# Supplies.net
KiCad netlist of a schematic drawn in Altium Designer
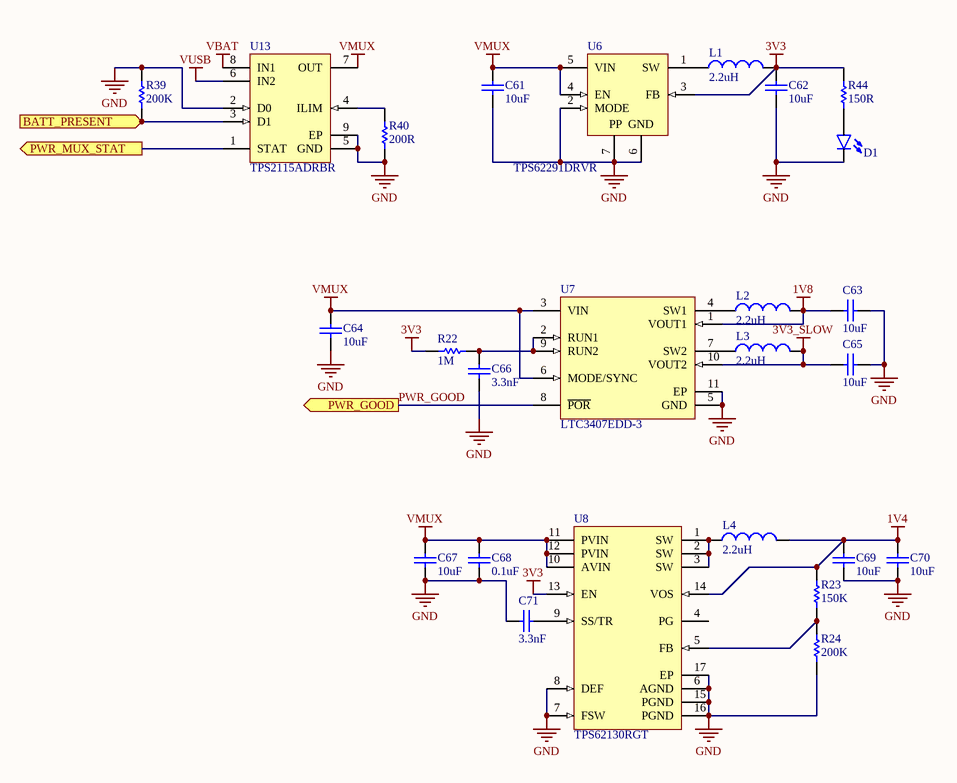
[diagram p0: Supplies.SchDoc]

(export (version "E")
  (design (tool "Eeschema 10.0.6"))
  (components
    (comp (ref "C61")
      (value "10uF")
      (footprint "C0402[1005X55]")
      (description "10uF 6.3V 20% 0402 (1005 Metric)")
      (fields (field (name "TOLERANCE") "20%") (field (name "PARTNUMBER") "GRM155R60J106ME44D"))
      (libsource (lib "Capacitors") (part "CAP_10uF_6.3V_0402_20%"))
    )
    (comp (ref "C62")
      (value "10uF")
      (footprint "C0402[1005X55]")
      (description "10uF 6.3V 20% 0402 (1005 Metric)")
      (fields (field (name "TOLERANCE") "20%") (field (name "PARTNUMBER") "GRM155R60J106ME44D"))
      (libsource (lib "Capacitors") (part "CAP_10uF_6.3V_0402_20%"))
    )
    (comp (ref "C63")
      (value "10uF")
      (footprint "C0402[1005X55]")
      (description "10uF 6.3V 20% 0402 (1005 Metric)")
      (fields (field (name "PARTNUMBER") "GRM155R60J106ME44D") (field (name "MANUFACTURER") "Murata"))
      (libsource (lib "Capacitors") (part "CAP_10uF_6.3V_0402_20%"))
    )
    (comp (ref "C64")
      (value "10uF")
      (footprint "C0402[1005X55]")
      (description "10uF 6.3V 20% 0402 (1005 Metric)")
      (fields (field (name "PARTNUMBER") "GRM155R60J106ME44D") (field (name "MANUFACTURER") "Murata"))
      (libsource (lib "Capacitors") (part "CAP_10uF_6.3V_0402_20%"))
    )
    (comp (ref "C65")
      (value "10uF")
      (footprint "C0402[1005X55]")
      (description "10uF 6.3V 20% 0402 (1005 Metric)")
      (fields (field (name "PARTNUMBER") "GRM155R60J106ME44D") (field (name "MANUFACTURER") "Murata"))
      (libsource (lib "Capacitors") (part "CAP_10uF_6.3V_0402_20%"))
    )
    (comp (ref "C66")
      (value "3.3nF")
      (footprint "C0402[1005X55]")
      (description "3.3nF 50V 10% 0402 (1005 Metric)")
      (fields (field (name "PARTNUMBER") "GRM155R71H332KA01D") (field (name "MANUFACTURER") "Murata"))
      (libsource (lib "Capacitors") (part "CAP_3.3nF_50V_0402_10%"))
    )
    (comp (ref "C67")
      (value "10uF")
      (footprint "C0402[1005X55]")
      (description "10uF 6.3V 20% 0402 (1005 Metric)")
      (fields (field (name "PARTNUMBER") "GRM155R60J106ME44D") (field (name "MANUFACTURER") "Murata"))
      (libsource (lib "Capacitors") (part "CAP_10uF_6.3V_0402_20%"))
    )
    (comp (ref "C68")
      (value "0.1uF")
      (footprint "C0402[1005X55]")
      (description "0.1uF 6.3V 10% 0402 (1005 Metric)")
      (fields (field (name "PARTNUMBER") "GRM155R70J104KA01D") (field (name "MANUFACTURER") "Murata"))
      (libsource (lib "Capacitors") (part "CAP_0.1uF_6.3V_0402_10%"))
    )
    (comp (ref "C69")
      (value "10uF")
      (footprint "C0402[1005X55]")
      (description "10uF 6.3V 20% 0402 (1005 Metric)")
      (fields (field (name "PARTNUMBER") "GRM155R60J106ME44D") (field (name "MANUFACTURER") "Murata"))
      (libsource (lib "Capacitors") (part "CAP_10uF_6.3V_0402_20%"))
    )
    (comp (ref "C70")
      (value "10uF")
      (footprint "C0402[1005X55]")
      (description "10uF 6.3V 20% 0402 (1005 Metric)")
      (fields (field (name "PARTNUMBER") "GRM155R60J106ME44D") (field (name "MANUFACTURER") "Murata"))
      (libsource (lib "Capacitors") (part "CAP_10uF_6.3V_0402_20%"))
    )
    (comp (ref "C71")
      (value "3.3nF")
      (footprint "C0402[1005X55]")
      (description "3.3nF 50V 10% 0402 (1005 Metric)")
      (fields (field (name "PARTNUMBER") "GRM155R71H332KA01D") (field (name "MANUFACTURER") "Murata"))
      (libsource (lib "Capacitors") (part "CAP_3.3nF_50V_0402_10%"))
    )
    (comp (ref "D1")
      (value "LED_0603_BLUE_5mA")
      (footprint "LED0603")
      (fields (field (name "PARTNUMBER") "LTST-C193TBKT-5A") (field (name "MANUFACTURER") "Lite-On Inc."))
      (libsource (lib "LEDs") (part "LED_0603_BLUE_5mA"))
    )
    (comp (ref "L1")
      (value "2.2uH")
      (footprint "IND0805")
      (description "2.2uH 20% 1.7A 0805")
      (fields (field (name "PARTNUMBER") "LQM21PN2R2MGHL") (field (name "MANUFACTURER") "Murata"))
      (libsource (lib "Inductors") (part "IND_2.2uH_1.7A_0805_20%"))
    )
    (comp (ref "L2")
      (value "2.2uH")
      (footprint "IND0603")
      (description "2.2uH 20% 750mA 0603")
      (fields (field (name "PARTNUMBER") "LQM18PZ2R2MCHD") (field (name "MANUFACTURER") "Murata"))
      (libsource (lib "Inductors") (part "IND_2.2uH_750mA_0603_20%"))
    )
    (comp (ref "L3")
      (value "2.2uH")
      (footprint "IND0603")
      (description "2.2uH 20% 750mA 0603")
      (fields (field (name "PARTNUMBER") "LQM18PZ2R2MCHD") (field (name "MANUFACTURER") "Murata"))
      (libsource (lib "Inductors") (part "IND_2.2uH_750mA_0603_20%"))
    )
    (comp (ref "L4")
      (value "2.2uH")
      (footprint "IND1008")
      (description "2.2uH 20% 3.3A 1008")
      (fields (field (name "PARTNUMBER") "DFE252012F-2R2M=P2") (field (name "MANUFACTURER") "Murata"))
      (libsource (lib "Inductors") (part "IND_2.2uH_3.3A_1008_20%"))
    )
    (comp (ref "R22")
      (value "1M")
      (footprint "R0402[1005]")
      (description "1M 0.063W 1% 0402 (1005 Metric)")
      (fields (field (name "MANUFACTURER") "KOA Speer") (field (name "PARTNUMBER") "RK73H1ETTP1004F"))
      (libsource (lib "Resistors") (part "RES_1M_0402_1%"))
    )
    (comp (ref "R23")
      (value "150K")
      (footprint "R0402[1005]")
      (description "150K 0.063W 1% 0402 (1005 Metric)")
      (fields (field (name "MANUFACTURER") "KOA Speer") (field (name "PARTNUMBER") "RK73H1ETTP1503F"))
      (libsource (lib "Resistors") (part "RES_150K_0402_1%"))
    )
    (comp (ref "R24")
      (value "200K")
      (footprint "R0402[1005]")
      (description "200K 0.063W 1% 0402 (1005 Metric)")
      (fields (field (name "MANUFACTURER") "KOA Speer") (field (name "PARTNUMBER") "RK73H1ETTP2003F"))
      (libsource (lib "Resistors") (part "RES_200K_0402_1%"))
    )
    (comp (ref "R39")
      (value "200K")
      (footprint "R0402[1005]")
      (description "200K 0.063W 1% 0402 (1005 Metric)")
      (fields (field (name "MANUFACTURER") "KOA Speer") (field (name "PARTNUMBER") "RK73H1ETTP2003F"))
      (libsource (lib "Resistors") (part "RES_200K_0402_1%"))
    )
    (comp (ref "R40")
      (value "200R")
      (footprint "R0402[1005]")
      (description "200R 0.063W 1% 0402 (1005 Metric)")
      (fields (field (name "MANUFACTURER") "KOA Speer") (field (name "PARTNUMBER") "RK73H1ETTP2000F"))
      (libsource (lib "Resistors") (part "RES_200R_0402_1%"))
    )
    (comp (ref "R44")
      (value "150R")
      (footprint "R0402[1005]")
      (description "150R 0.063W 1% 0402 (1005 Metric)")
      (fields (field (name "MANUFACTURER") "KOA Speer") (field (name "PARTNUMBER") "RK73H1ETTP1500F"))
      (libsource (lib "Resistors") (part "RES_150R_0402_1%"))
    )
    (comp (ref "U6")
      (value "TPS62291DRVR")
      (footprint "WSON-6")
      (description "Voltage Regulators - Switching Regulators 2.25MHz 1A Step-Down Cnvrtr 3.3V Output")
      (fields (field (name "MANUFACTURER") "Texas Instruments"))
      (libsource (lib "ICs") (part "TPS62291DRVR"))
    )
    (comp (ref "U7")
      (value "LTC3407EDD-3")
      (footprint "VSON-10 (3mmx3mm)")
      (fields (field (name "MANUFACTURER") "Linear Technology"))
      (libsource (lib "ICs") (part "LTC3407EDD-3"))
    )
    (comp (ref "U8")
      (value "TPS62130RGT")
      (footprint "QFN-16")
      (fields (field (name "MANUFACTURER") "Texas Instruments"))
      (libsource (lib "ICs") (part "TPS62130RGT"))
    )
    (comp (ref "U13")
      (value "TPS2115ADRBR")
      (footprint "VSON-8 (3x3MM)")
      (description "Power Switch ICs - Power Distribution Autoswitching Pwr Mux")
      (fields (field (name "MANUFACTURER") "Texas Instruments"))
      (libsource (lib "ICs") (part "TPS2115ADRBR"))
    )
  )
  (nets
    (net (code "1") (name "/BATT_PRESENT") (class "Default")
      (node (ref "R39") (pin "1") (pinfunction "1_1") (pintype "passive"))
      (node (ref "U13") (pin "3") (pinfunction "D1_3") (pintype "input"))
    )
    (net (code "2") (name "/PWR_GOOD") (class "Default")
      (node (ref "U7") (pin "8") (pinfunction "~{POR}_8") (pintype "open_collector"))
    )
    (net (code "3") (name "/PWR_MUX_STAT") (class "Default")
      (node (ref "U13") (pin "1") (pinfunction "STAT_1") (pintype "tri_state"))
    )
    (net (code "4") (name "1V4") (class "Default")
      (node (ref "C69") (pin "2") (pinfunction "2_2") (pintype "passive"))
      (node (ref "C70") (pin "2") (pinfunction "2_2") (pintype "passive"))
      (node (ref "L4") (pin "2") (pinfunction "2_2") (pintype "passive"))
      (node (ref "R23") (pin "2") (pinfunction "2_2") (pintype "passive"))
      (node (ref "U8") (pin "14") (pinfunction "VOS_14") (pintype "input"))
    )
    (net (code "5") (name "1V8") (class "Default")
      (node (ref "C63") (pin "2") (pinfunction "2_2") (pintype "passive"))
      (node (ref "L2") (pin "2") (pinfunction "2_2") (pintype "passive"))
      (node (ref "U7") (pin "1") (pinfunction "VOUT1_1") (pintype "input"))
    )
    (net (code "6") (name "3V3") (class "Default")
      (node (ref "C62") (pin "2") (pinfunction "2_2") (pintype "passive"))
      (node (ref "L1") (pin "2") (pinfunction "2_2") (pintype "passive"))
      (node (ref "R22") (pin "2") (pinfunction "2_2") (pintype "passive"))
      (node (ref "R44") (pin "2") (pinfunction "2_2") (pintype "passive"))
      (node (ref "U6") (pin "3") (pinfunction "FB_3") (pintype "input"))
      (node (ref "U8") (pin "13") (pinfunction "EN_13") (pintype "input"))
    )
    (net (code "7") (name "3V3_SLOW") (class "Default")
      (node (ref "C65") (pin "1") (pinfunction "1_1") (pintype "passive"))
      (node (ref "L3") (pin "2") (pinfunction "2_2") (pintype "passive"))
      (node (ref "U7") (pin "10") (pinfunction "VOUT2_10") (pintype "input"))
    )
    (net (code "8") (name "GND") (class "Default")
      (node (ref "C61") (pin "1") (pinfunction "1_1") (pintype "passive"))
      (node (ref "C62") (pin "1") (pinfunction "1_1") (pintype "passive"))
      (node (ref "C63") (pin "1") (pinfunction "1_1") (pintype "passive"))
      (node (ref "C64") (pin "1") (pinfunction "1_1") (pintype "passive"))
      (node (ref "C65") (pin "2") (pinfunction "2_2") (pintype "passive"))
      (node (ref "C66") (pin "1") (pinfunction "1_1") (pintype "passive"))
      (node (ref "C67") (pin "1") (pinfunction "1_1") (pintype "passive"))
      (node (ref "C68") (pin "1") (pinfunction "1_1") (pintype "passive"))
      (node (ref "C69") (pin "1") (pinfunction "1_1") (pintype "passive"))
      (node (ref "C70") (pin "1") (pinfunction "1_1") (pintype "passive"))
      (node (ref "C71") (pin "1") (pinfunction "1_1") (pintype "passive"))
      (node (ref "D1") (pin "C") (pinfunction "C_C") (pintype "passive"))
      (node (ref "R24") (pin "1") (pinfunction "1_1") (pintype "passive"))
      (node (ref "R39") (pin "2") (pinfunction "2_2") (pintype "passive"))
      (node (ref "R40") (pin "1") (pinfunction "1_1") (pintype "passive"))
      (node (ref "U13") (pin "2") (pinfunction "D0_2") (pintype "input"))
      (node (ref "U13") (pin "5") (pinfunction "GND_5") (pintype "power_in"))
      (node (ref "U13") (pin "9") (pinfunction "EP_9") (pintype "power_in"))
      (node (ref "U6") (pin "2") (pinfunction "MODE_2") (pintype "input"))
      (node (ref "U6") (pin "6") (pinfunction "GND_6") (pintype "power_in"))
      (node (ref "U6") (pin "7") (pinfunction "EP_7") (pintype "passive"))
      (node (ref "U7") (pin "11") (pinfunction "EP_11") (pintype "power_in"))
      (node (ref "U7") (pin "5") (pinfunction "GND_5") (pintype "power_in"))
      (node (ref "U8") (pin "15") (pinfunction "PGND_15") (pintype "power_in"))
      (node (ref "U8") (pin "16") (pinfunction "PGND_16") (pintype "power_in"))
      (node (ref "U8") (pin "17") (pinfunction "EP_17") (pintype "power_in"))
      (node (ref "U8") (pin "6") (pinfunction "AGND_6") (pintype "power_in"))
      (node (ref "U8") (pin "7") (pinfunction "FSW_7") (pintype "input"))
      (node (ref "U8") (pin "8") (pinfunction "DEF_8") (pintype "input"))
    )
    (net (code "9") (name "Net-(D1-PadA)") (class "Default")
      (node (ref "D1") (pin "A") (pinfunction "A_A") (pintype "passive"))
      (node (ref "R44") (pin "1") (pinfunction "1_1") (pintype "passive"))
    )
    (net (code "10") (name "Net-(L4-Pad1)") (class "Default")
      (node (ref "L4") (pin "1") (pinfunction "1_1") (pintype "passive"))
      (node (ref "U8") (pin "1") (pinfunction "SW_1") (pintype "power_in"))
      (node (ref "U8") (pin "2") (pinfunction "SW_2") (pintype "power_in"))
      (node (ref "U8") (pin "3") (pinfunction "SW_3") (pintype "power_in"))
    )
    (net (code "11") (name "Net-(U6-SW)") (class "Default")
      (node (ref "L1") (pin "1") (pinfunction "1_1") (pintype "passive"))
      (node (ref "U6") (pin "1") (pinfunction "SW_1") (pintype "power_in"))
    )
    (net (code "12") (name "Net-(U7-RUN1)") (class "Default")
      (node (ref "C66") (pin "2") (pinfunction "2_2") (pintype "passive"))
      (node (ref "R22") (pin "1") (pinfunction "1_1") (pintype "passive"))
      (node (ref "U7") (pin "2") (pinfunction "RUN1_2") (pintype "input"))
      (node (ref "U7") (pin "9") (pinfunction "RUN2_9") (pintype "input"))
    )
    (net (code "13") (name "Net-(U7-SW1)") (class "Default")
      (node (ref "L2") (pin "1") (pinfunction "1_1") (pintype "passive"))
      (node (ref "U7") (pin "4") (pinfunction "SW1_4") (pintype "power_in"))
    )
    (net (code "14") (name "Net-(U7-SW2)") (class "Default")
      (node (ref "L3") (pin "1") (pinfunction "1_1") (pintype "passive"))
      (node (ref "U7") (pin "7") (pinfunction "SW2_7") (pintype "power_in"))
    )
    (net (code "15") (name "Net-(U8-FB)") (class "Default")
      (node (ref "R23") (pin "1") (pinfunction "1_1") (pintype "passive"))
      (node (ref "R24") (pin "2") (pinfunction "2_2") (pintype "passive"))
      (node (ref "U8") (pin "5") (pinfunction "FB_5") (pintype "input"))
    )
    (net (code "16") (name "Net-(U8-SS{slash}TR)") (class "Default")
      (node (ref "C71") (pin "2") (pinfunction "2_2") (pintype "passive"))
      (node (ref "U8") (pin "9") (pinfunction "SS/TR_9") (pintype "input"))
    )
    (net (code "17") (name "Net-(U13-ILIM)") (class "Default")
      (node (ref "R40") (pin "2") (pinfunction "2_2") (pintype "passive"))
      (node (ref "U13") (pin "4") (pinfunction "ILIM_4") (pintype "input"))
    )
    (net (code "18") (name "VBAT") (class "Default")
      (node (ref "U13") (pin "8") (pinfunction "IN1_8") (pintype "power_in"))
    )
    (net (code "19") (name "VMUX") (class "Default")
      (node (ref "C61") (pin "2") (pinfunction "2_2") (pintype "passive"))
      (node (ref "C64") (pin "2") (pinfunction "2_2") (pintype "passive"))
      (node (ref "C67") (pin "2") (pinfunction "2_2") (pintype "passive"))
      (node (ref "C68") (pin "2") (pinfunction "2_2") (pintype "passive"))
      (node (ref "U13") (pin "7") (pinfunction "OUT_7") (pintype "power_in"))
      (node (ref "U6") (pin "4") (pinfunction "EN_4") (pintype "input"))
      (node (ref "U6") (pin "5") (pinfunction "VIN_5") (pintype "power_in"))
      (node (ref "U7") (pin "3") (pinfunction "VIN_3") (pintype "power_in"))
      (node (ref "U7") (pin "6") (pinfunction "MODE/SYNC_6") (pintype "input"))
      (node (ref "U8") (pin "10") (pinfunction "AVIN_10") (pintype "power_in"))
      (node (ref "U8") (pin "11") (pinfunction "PVIN_11") (pintype "power_in"))
      (node (ref "U8") (pin "12") (pinfunction "PVIN_12") (pintype "power_in"))
    )
    (net (code "20") (name "VUSB") (class "Default")
      (node (ref "U13") (pin "6") (pinfunction "IN2_6") (pintype "power_in"))
    )
    (net (code "21") (name "unconnected-(U8-PG-Pad4)") (class "Default")
      (node (ref "U8") (pin "4") (pinfunction "PG_4") (pintype "tri_state"))
    )
  )
)
